# Opamps.net
KiCad netlist of a schematic drawn in Altium Designer
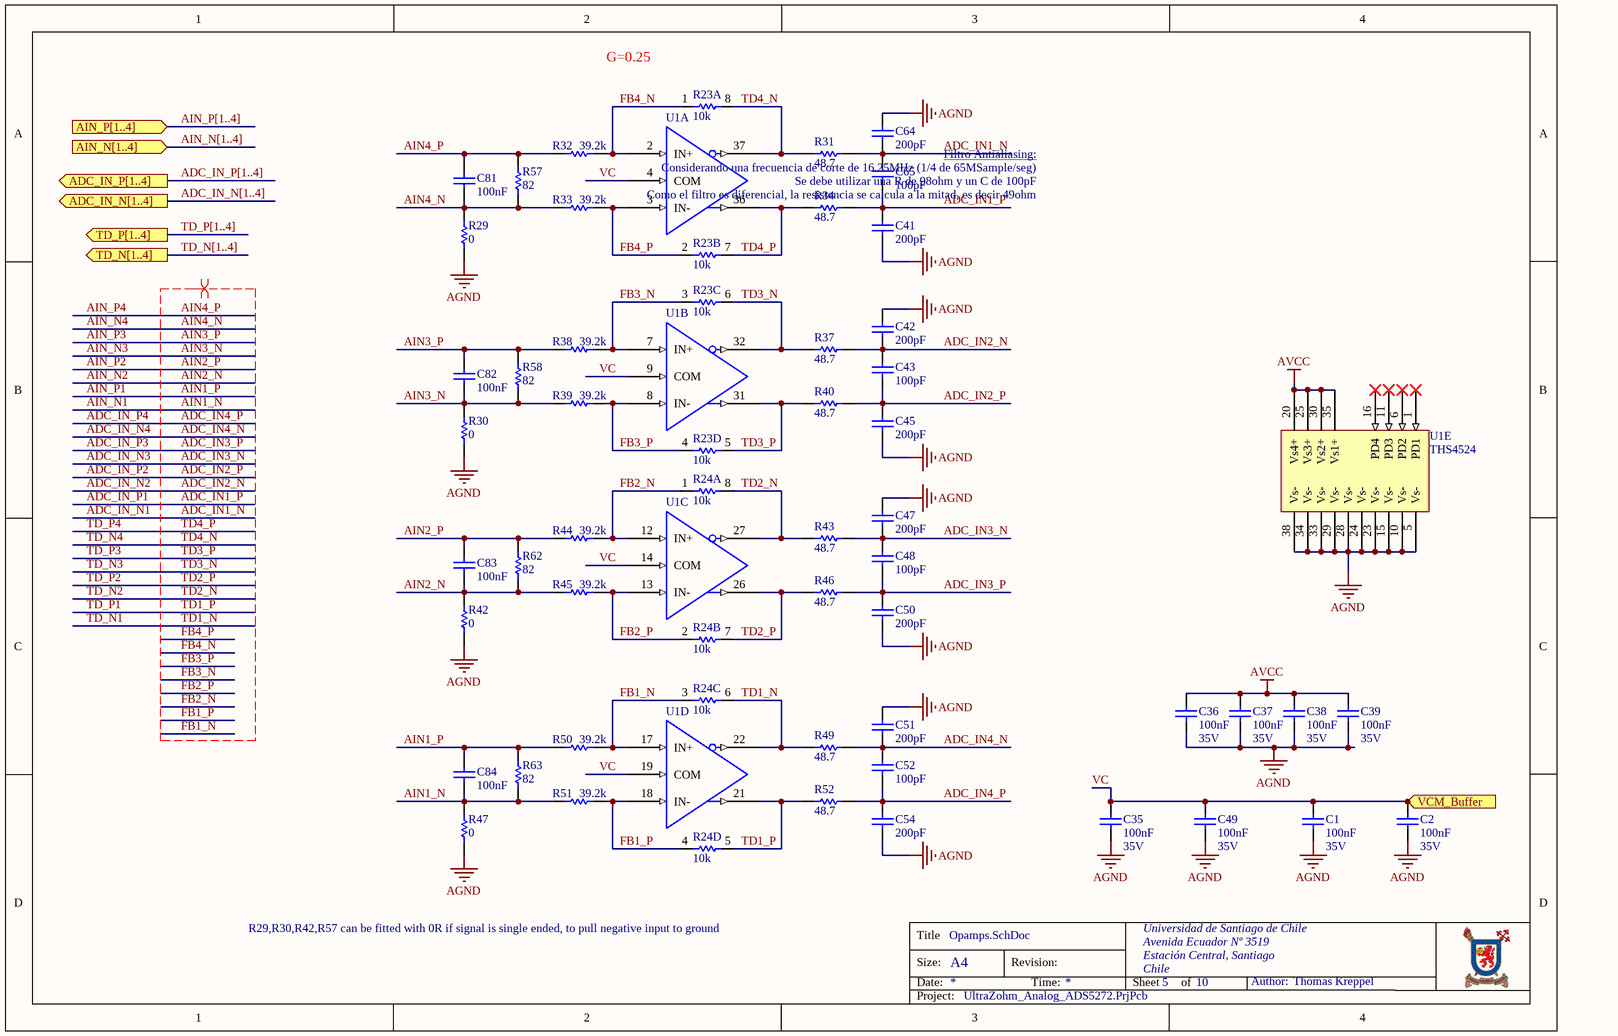
[diagram p0: Opamps.SchDoc]

(export (version "E")
  (design (tool "Eeschema 10.0.6"))
  (components
    (comp (ref "C1")
      (value "100nF")
      (footprint "CAP_0603")
      (description "Capacitor")
      (fields
        (field (name "MPN") "C0603C104M5RACTU")
        (field (name "MF") "KEMET")
        (field (name "VOLTAGE") "35V")
        (field (name "PUBLISHER") "Altium Limited")
      )
      (libsource (lib "Componentes_SOC") (part "Cap_0603"))
    )
    (comp (ref "C2")
      (value "100nF")
      (footprint "CAP_0603")
      (description "Capacitor")
      (fields
        (field (name "MPN") "C0603C104M5RACTU")
        (field (name "MF") "KEMET")
        (field (name "VOLTAGE") "35V")
        (field (name "PUBLISHER") "Altium Limited")
      )
      (libsource (lib "Componentes_SOC") (part "Cap_0603"))
    )
    (comp (ref "C35")
      (value "100nF")
      (footprint "CAP_0603")
      (description "Capacitor")
      (fields
        (field (name "MPN") "C0603C104M5RACTU")
        (field (name "MF") "KEMET")
        (field (name "VOLTAGE") "35V")
        (field (name "PUBLISHER") "Altium Limited")
      )
      (libsource (lib "Componentes_SOC") (part "Cap_0603"))
    )
    (comp (ref "C36")
      (value "100nF")
      (footprint "CAP_0603")
      (description "Capacitor")
      (fields
        (field (name "MPN") "C0603C104M5RACTU")
        (field (name "MF") "KEMET")
        (field (name "VOLTAGE") "35V")
        (field (name "PUBLISHER") "Altium Limited")
      )
      (libsource (lib "Componentes_SOC") (part "Cap_0603"))
    )
    (comp (ref "C37")
      (value "100nF")
      (footprint "CAP_0603")
      (description "Capacitor")
      (fields
        (field (name "MPN") "C0603C104M5RACTU")
        (field (name "MF") "KEMET")
        (field (name "VOLTAGE") "35V")
        (field (name "PUBLISHER") "Altium Limited")
      )
      (libsource (lib "Componentes_SOC") (part "Cap_0603"))
    )
    (comp (ref "C38")
      (value "100nF")
      (footprint "CAP_0603")
      (description "Capacitor")
      (fields
        (field (name "MPN") "C0603C104M5RACTU")
        (field (name "MF") "KEMET")
        (field (name "VOLTAGE") "35V")
        (field (name "PUBLISHER") "Altium Limited")
      )
      (libsource (lib "Componentes_SOC") (part "Cap_0603"))
    )
    (comp (ref "C39")
      (value "100nF")
      (footprint "CAP_0603")
      (description "Capacitor")
      (fields
        (field (name "MPN") "C0603C104M5RACTU")
        (field (name "MF") "KEMET")
        (field (name "VOLTAGE") "35V")
        (field (name "PUBLISHER") "Altium Limited")
      )
      (libsource (lib "Componentes_SOC") (part "Cap_0603"))
    )
    (comp (ref "C41")
      (value "200pF")
      (footprint "CAP_0603")
      (description "Capacitor")
      (fields
        (field (name "MPN") "0603N201J500CT")
        (field (name "MF") "Walsin")
        (field (name "PUBLISHER") "Altium Limited")
      )
      (libsource (lib "Componentes_SOC") (part "Cap_0603"))
    )
    (comp (ref "C42")
      (value "200pF")
      (footprint "CAP_0603")
      (description "Capacitor")
      (fields
        (field (name "MPN") "0603N201J500CT")
        (field (name "MF") "Walsin")
        (field (name "PUBLISHER") "Altium Limited")
      )
      (libsource (lib "Componentes_SOC") (part "Cap_0603"))
    )
    (comp (ref "C43")
      (value "100pF")
      (footprint "CAP_0603")
      (description "Capacitor")
      (fields
        (field (name "MPN") "885012006023")
        (field (name "MF") "Würth Elektronik")
        (field (name "PUBLISHER") "Altium Limited")
      )
      (libsource (lib "Componentes_SOC") (part "Cap_0603"))
    )
    (comp (ref "C45")
      (value "200pF")
      (footprint "CAP_0603")
      (description "Capacitor")
      (fields
        (field (name "MPN") "0603N201J500CT")
        (field (name "MF") "Walsin")
        (field (name "PUBLISHER") "Altium Limited")
      )
      (libsource (lib "Componentes_SOC") (part "Cap_0603"))
    )
    (comp (ref "C47")
      (value "200pF")
      (footprint "CAP_0603")
      (description "Capacitor")
      (fields
        (field (name "MPN") "0603N201J500CT")
        (field (name "MF") "Walsin")
        (field (name "PUBLISHER") "Altium Limited")
      )
      (libsource (lib "Componentes_SOC") (part "Cap_0603"))
    )
    (comp (ref "C48")
      (value "100pF")
      (footprint "CAP_0603")
      (description "Capacitor")
      (fields
        (field (name "MPN") "885012006023")
        (field (name "MF") "Würth Elektronik")
        (field (name "PUBLISHER") "Altium Limited")
      )
      (libsource (lib "Componentes_SOC") (part "Cap_0603"))
    )
    (comp (ref "C49")
      (value "100nF")
      (footprint "CAP_0603")
      (description "Capacitor")
      (fields
        (field (name "MPN") "C0603C104M5RACTU")
        (field (name "MF") "KEMET")
        (field (name "VOLTAGE") "35V")
        (field (name "PUBLISHER") "Altium Limited")
      )
      (libsource (lib "Componentes_SOC") (part "Cap_0603"))
    )
    (comp (ref "C50")
      (value "200pF")
      (footprint "CAP_0603")
      (description "Capacitor")
      (fields
        (field (name "MPN") "0603N201J500CT")
        (field (name "MF") "Walsin")
        (field (name "PUBLISHER") "Altium Limited")
      )
      (libsource (lib "Componentes_SOC") (part "Cap_0603"))
    )
    (comp (ref "C51")
      (value "200pF")
      (footprint "CAP_0603")
      (description "Capacitor")
      (fields
        (field (name "MPN") "0603N201J500CT")
        (field (name "MF") "Walsin")
        (field (name "PUBLISHER") "Altium Limited")
      )
      (libsource (lib "Componentes_SOC") (part "Cap_0603"))
    )
    (comp (ref "C52")
      (value "100pF")
      (footprint "CAP_0603")
      (description "Capacitor")
      (fields
        (field (name "MPN") "885012006023")
        (field (name "MF") "Würth Elektronik")
        (field (name "PUBLISHER") "Altium Limited")
      )
      (libsource (lib "Componentes_SOC") (part "Cap_0603"))
    )
    (comp (ref "C54")
      (value "200pF")
      (footprint "CAP_0603")
      (description "Capacitor")
      (fields
        (field (name "MPN") "0603N201J500CT")
        (field (name "MF") "Walsin")
        (field (name "PUBLISHER") "Altium Limited")
      )
      (libsource (lib "Componentes_SOC") (part "Cap_0603"))
    )
    (comp (ref "C64")
      (value "200pF")
      (footprint "CAP_0603")
      (description "Capacitor")
      (fields
        (field (name "MPN") "0603N201J500CT")
        (field (name "MF") "Walsin")
        (field (name "PUBLISHER") "Altium Limited")
      )
      (libsource (lib "Componentes_SOC") (part "Cap_0603"))
    )
    (comp (ref "C65")
      (value "100pF")
      (footprint "CAP_0603")
      (description "Capacitor")
      (fields
        (field (name "MPN") "885012006023")
        (field (name "MF") "Würth Elektronik")
        (field (name "PUBLISHER") "Altium Limited")
      )
      (libsource (lib "Componentes_SOC") (part "Cap_0603"))
    )
    (comp (ref "C81")
      (value "100nF")
      (footprint "RES_1206")
      (description "Capacitor")
      (fields (field (name "VOLTAGE") "25V") (field (name "MF") "KEMET"))
      (libsource (lib "Componentes_SOC") (part "Cap_1206"))
    )
    (comp (ref "C82")
      (value "100nF")
      (footprint "RES_1206")
      (description "Capacitor")
      (fields (field (name "VOLTAGE") "25V") (field (name "MF") "KEMET"))
      (libsource (lib "Componentes_SOC") (part "Cap_1206"))
    )
    (comp (ref "C83")
      (value "100nF")
      (footprint "RES_1206")
      (description "Capacitor")
      (fields (field (name "VOLTAGE") "25V") (field (name "MF") "KEMET"))
      (libsource (lib "Componentes_SOC") (part "Cap_1206"))
    )
    (comp (ref "C84")
      (value "100nF")
      (footprint "RES_1206")
      (description "Capacitor")
      (fields (field (name "VOLTAGE") "25V") (field (name "MF") "KEMET"))
      (libsource (lib "Componentes_SOC") (part "Cap_1206"))
    )
    (comp (ref "R23")
      (value "10k")
      (footprint "CAC-80P320X160-8N")
      (description "Chip Resistor Array 0606, 4xR")
      (fields (field (name "MANUFACTURER") "Vishay") (field (name "CREATED") "Kreppel_0420"))
      (libsource (lib "Componentes_SOC") (part "ResArray 1206"))
    )
    (comp (ref "R24")
      (value "10k")
      (footprint "CAC-80P320X160-8N")
      (description "Chip Resistor Array 0606, 4xR")
      (fields (field (name "MANUFACTURER") "Vishay") (field (name "CREATED") "Kreppel_0420"))
      (libsource (lib "Componentes_SOC") (part "ResArray 1206"))
    )
    (comp (ref "R29")
      (value "0")
      (footprint "RES_0603")
      (fields (field (name "TOLERANCE") "1%") (field (name "PUBLISHER") "Altium Limited"))
      (libsource (lib "Componentes_SOC") (part "Res0603"))
    )
    (comp (ref "R30")
      (value "0")
      (footprint "RES_0603")
      (fields (field (name "TOLERANCE") "1%") (field (name "PUBLISHER") "Altium Limited"))
      (libsource (lib "Componentes_SOC") (part "Res0603"))
    )
    (comp (ref "R31")
      (value "48.7")
      (footprint "RES_0603")
      (fields (field (name "TOLERANCE") "0.1%") (field (name "PUBLISHER") "Altium Limited"))
      (libsource (lib "Componentes_SOC") (part "Res0603"))
    )
    (comp (ref "R32")
      (value "39.2k")
      (footprint "RES_0603")
      (fields (field (name "TOLERANCE") "0.1%") (field (name "PUBLISHER") "Altium Limited"))
      (libsource (lib "Componentes_SOC") (part "Res0603"))
    )
    (comp (ref "R33")
      (value "39.2k")
      (footprint "RES_0603")
      (fields (field (name "TOLERANCE") "0.1%") (field (name "PUBLISHER") "Altium Limited"))
      (libsource (lib "Componentes_SOC") (part "Res0603"))
    )
    (comp (ref "R34")
      (value "48.7")
      (footprint "RES_0603")
      (fields (field (name "TOLERANCE") "0.1%") (field (name "PUBLISHER") "Altium Limited"))
      (libsource (lib "Componentes_SOC") (part "Res0603"))
    )
    (comp (ref "R37")
      (value "48.7")
      (footprint "RES_0603")
      (fields (field (name "TOLERANCE") "0.1%") (field (name "PUBLISHER") "Altium Limited"))
      (libsource (lib "Componentes_SOC") (part "Res0603"))
    )
    (comp (ref "R38")
      (value "39.2k")
      (footprint "RES_0603")
      (fields (field (name "TOLERANCE") "0.1%") (field (name "PUBLISHER") "Altium Limited"))
      (libsource (lib "Componentes_SOC") (part "Res0603"))
    )
    (comp (ref "R39")
      (value "39.2k")
      (footprint "RES_0603")
      (fields (field (name "TOLERANCE") "0.1%") (field (name "PUBLISHER") "Altium Limited"))
      (libsource (lib "Componentes_SOC") (part "Res0603"))
    )
    (comp (ref "R40")
      (value "48.7")
      (footprint "RES_0603")
      (fields (field (name "TOLERANCE") "0.1%") (field (name "PUBLISHER") "Altium Limited"))
      (libsource (lib "Componentes_SOC") (part "Res0603"))
    )
    (comp (ref "R42")
      (value "0")
      (footprint "RES_0603")
      (fields (field (name "TOLERANCE") "1%") (field (name "PUBLISHER") "Altium Limited"))
      (libsource (lib "Componentes_SOC") (part "Res0603"))
    )
    (comp (ref "R43")
      (value "48.7")
      (footprint "RES_0603")
      (fields (field (name "TOLERANCE") "0.1%") (field (name "PUBLISHER") "Altium Limited"))
      (libsource (lib "Componentes_SOC") (part "Res0603"))
    )
    (comp (ref "R44")
      (value "39.2k")
      (footprint "RES_0603")
      (fields (field (name "TOLERANCE") "0.1%") (field (name "PUBLISHER") "Altium Limited"))
      (libsource (lib "Componentes_SOC") (part "Res0603"))
    )
    (comp (ref "R45")
      (value "39.2k")
      (footprint "RES_0603")
      (fields (field (name "TOLERANCE") "0.1%") (field (name "PUBLISHER") "Altium Limited"))
      (libsource (lib "Componentes_SOC") (part "Res0603"))
    )
    (comp (ref "R46")
      (value "48.7")
      (footprint "RES_0603")
      (fields (field (name "TOLERANCE") "0.1%") (field (name "PUBLISHER") "Altium Limited"))
      (libsource (lib "Componentes_SOC") (part "Res0603"))
    )
    (comp (ref "R47")
      (value "0")
      (footprint "RES_0603")
      (fields (field (name "TOLERANCE") "1%") (field (name "PUBLISHER") "Altium Limited"))
      (libsource (lib "Componentes_SOC") (part "Res0603"))
    )
    (comp (ref "R49")
      (value "48.7")
      (footprint "RES_0603")
      (fields (field (name "TOLERANCE") "0.1%") (field (name "PUBLISHER") "Altium Limited"))
      (libsource (lib "Componentes_SOC") (part "Res0603"))
    )
    (comp (ref "R50")
      (value "39.2k")
      (footprint "RES_0603")
      (fields (field (name "TOLERANCE") "0.1%") (field (name "PUBLISHER") "Altium Limited"))
      (libsource (lib "Componentes_SOC") (part "Res0603"))
    )
    (comp (ref "R51")
      (value "39.2k")
      (footprint "RES_0603")
      (fields (field (name "TOLERANCE") "0.1%") (field (name "PUBLISHER") "Altium Limited"))
      (libsource (lib "Componentes_SOC") (part "Res0603"))
    )
    (comp (ref "R52")
      (value "48.7")
      (footprint "RES_0603")
      (fields (field (name "TOLERANCE") "0.1%") (field (name "PUBLISHER") "Altium Limited"))
      (libsource (lib "Componentes_SOC") (part "Res0603"))
    )
    (comp (ref "R57")
      (value "82")
      (footprint "RES_1206")
      (description "Limiter Resistor")
      (fields (field (name "TOLERANCE") "0.1%") (field (name "PUBLISHER") "Altium Limited"))
      (libsource (lib "Miscellaneous Devices") (part "Res Semi"))
    )
    (comp (ref "R58")
      (value "82")
      (footprint "RES_1206")
      (description "Limiter Resistor")
      (fields (field (name "TOLERANCE") "0.1%") (field (name "PUBLISHER") "Altium Limited"))
      (libsource (lib "Miscellaneous Devices") (part "Res Semi"))
    )
    (comp (ref "R62")
      (value "82")
      (footprint "RES_1206")
      (description "Limiter Resistor")
      (fields (field (name "TOLERANCE") "0.1%") (field (name "PUBLISHER") "Altium Limited"))
      (libsource (lib "Miscellaneous Devices") (part "Res Semi"))
    )
    (comp (ref "R63")
      (value "82")
      (footprint "RES_1206")
      (description "Limiter Resistor")
      (fields (field (name "TOLERANCE") "0.1%") (field (name "PUBLISHER") "Altium Limited"))
      (libsource (lib "Miscellaneous Devices") (part "Res Semi"))
    )
    (comp (ref "U1")
      (value "THS4524")
      (footprint "THS4524 Footprint")
      (description "Quad Channel fully differential Amplilfier")
      (fields (field (name "MANUFACTURER") "Texas Instruments") (field (name "CREATED") "20190720_Kreppel"))
      (libsource (lib "") (part "THS4524_1_1"))
    )
  )
  (nets
    (net (code "1") (name "/ADC_IN_N1") (class "Default")
      (node (ref "C64") (pin "2") (pinfunction "2_2") (pintype "passive"))
      (node (ref "C65") (pin "1") (pinfunction "1_1") (pintype "passive"))
      (node (ref "R31") (pin "1") (pinfunction "1_1") (pintype "passive"))
    )
    (net (code "2") (name "/ADC_IN_N2") (class "Default")
      (node (ref "C42") (pin "2") (pinfunction "2_2") (pintype "passive"))
      (node (ref "C43") (pin "1") (pinfunction "1_1") (pintype "passive"))
      (node (ref "R37") (pin "1") (pinfunction "1_1") (pintype "passive"))
    )
    (net (code "3") (name "/ADC_IN_N3") (class "Default")
      (node (ref "C47") (pin "2") (pinfunction "2_2") (pintype "passive"))
      (node (ref "C48") (pin "1") (pinfunction "1_1") (pintype "passive"))
      (node (ref "R43") (pin "1") (pinfunction "1_1") (pintype "passive"))
    )
    (net (code "4") (name "/ADC_IN_N4") (class "Default")
      (node (ref "C51") (pin "2") (pinfunction "2_2") (pintype "passive"))
      (node (ref "C52") (pin "1") (pinfunction "1_1") (pintype "passive"))
      (node (ref "R49") (pin "1") (pinfunction "1_1") (pintype "passive"))
    )
    (net (code "6") (name "/ADC_IN_P1") (class "Default")
      (node (ref "C41") (pin "1") (pinfunction "1_1") (pintype "passive"))
      (node (ref "C65") (pin "2") (pinfunction "2_2") (pintype "passive"))
      (node (ref "R34") (pin "1") (pinfunction "1_1") (pintype "passive"))
    )
    (net (code "7") (name "/ADC_IN_P2") (class "Default")
      (node (ref "C43") (pin "2") (pinfunction "2_2") (pintype "passive"))
      (node (ref "C45") (pin "1") (pinfunction "1_1") (pintype "passive"))
      (node (ref "R40") (pin "1") (pinfunction "1_1") (pintype "passive"))
    )
    (net (code "8") (name "/ADC_IN_P3") (class "Default")
      (node (ref "C48") (pin "2") (pinfunction "2_2") (pintype "passive"))
      (node (ref "C50") (pin "1") (pinfunction "1_1") (pintype "passive"))
      (node (ref "R46") (pin "1") (pinfunction "1_1") (pintype "passive"))
    )
    (net (code "9") (name "/ADC_IN_P4") (class "Default")
      (node (ref "C52") (pin "2") (pinfunction "2_2") (pintype "passive"))
      (node (ref "C54") (pin "1") (pinfunction "1_1") (pintype "passive"))
      (node (ref "R52") (pin "1") (pinfunction "1_1") (pintype "passive"))
    )
    (net (code "11") (name "/AIN_N1") (class "Default")
      (node (ref "C84") (pin "2") (pinfunction "2_2") (pintype "passive"))
      (node (ref "R47") (pin "1") (pinfunction "1_1") (pintype "passive"))
      (node (ref "R51") (pin "2") (pinfunction "2_2") (pintype "passive"))
      (node (ref "R63") (pin "2") (pinfunction "2_2") (pintype "passive"))
    )
    (net (code "12") (name "/AIN_N2") (class "Default")
      (node (ref "C83") (pin "2") (pinfunction "2_2") (pintype "passive"))
      (node (ref "R42") (pin "1") (pinfunction "1_1") (pintype "passive"))
      (node (ref "R45") (pin "2") (pinfunction "2_2") (pintype "passive"))
      (node (ref "R62") (pin "2") (pinfunction "2_2") (pintype "passive"))
    )
    (net (code "13") (name "/AIN_N3") (class "Default")
      (node (ref "C82") (pin "2") (pinfunction "2_2") (pintype "passive"))
      (node (ref "R30") (pin "1") (pinfunction "1_1") (pintype "passive"))
      (node (ref "R39") (pin "2") (pinfunction "2_2") (pintype "passive"))
      (node (ref "R58") (pin "2") (pinfunction "2_2") (pintype "passive"))
    )
    (net (code "14") (name "/AIN_N4") (class "Default")
      (node (ref "C81") (pin "2") (pinfunction "2_2") (pintype "passive"))
      (node (ref "R29") (pin "1") (pinfunction "1_1") (pintype "passive"))
      (node (ref "R33") (pin "2") (pinfunction "2_2") (pintype "passive"))
      (node (ref "R57") (pin "2") (pinfunction "2_2") (pintype "passive"))
    )
    (net (code "16") (name "/AIN_P1") (class "Default")
      (node (ref "C84") (pin "1") (pinfunction "1_1") (pintype "passive"))
      (node (ref "R50") (pin "2") (pinfunction "2_2") (pintype "passive"))
      (node (ref "R63") (pin "1") (pinfunction "1_1") (pintype "passive"))
    )
    (net (code "17") (name "/AIN_P2") (class "Default")
      (node (ref "C83") (pin "1") (pinfunction "1_1") (pintype "passive"))
      (node (ref "R44") (pin "2") (pinfunction "2_2") (pintype "passive"))
      (node (ref "R62") (pin "1") (pinfunction "1_1") (pintype "passive"))
    )
    (net (code "18") (name "/AIN_P3") (class "Default")
      (node (ref "C82") (pin "1") (pinfunction "1_1") (pintype "passive"))
      (node (ref "R38") (pin "2") (pinfunction "2_2") (pintype "passive"))
      (node (ref "R58") (pin "1") (pinfunction "1_1") (pintype "passive"))
    )
    (net (code "19") (name "/AIN_P4") (class "Default")
      (node (ref "C81") (pin "1") (pinfunction "1_1") (pintype "passive"))
      (node (ref "R32") (pin "2") (pinfunction "2_2") (pintype "passive"))
      (node (ref "R57") (pin "1") (pinfunction "1_1") (pintype "passive"))
    )
    (net (code "21") (name "/FB1_N") (class "Default")
      (node (ref "R24") (pin "3") (pinfunction "1_3") (pintype "passive"))
      (node (ref "R50") (pin "1") (pinfunction "1_1") (pintype "passive"))
      (node (ref "U1") (pin "17") (pinfunction "IN+_17") (pintype "input"))
    )
    (net (code "22") (name "/FB1_P") (class "Default")
      (node (ref "R24") (pin "4") (pinfunction "1_4") (pintype "passive"))
      (node (ref "R51") (pin "1") (pinfunction "1_1") (pintype "passive"))
      (node (ref "U1") (pin "18") (pinfunction "IN-_18") (pintype "input"))
    )
    (net (code "23") (name "/FB2_N") (class "Default")
      (node (ref "R24") (pin "1") (pinfunction "1_1") (pintype "passive"))
      (node (ref "R44") (pin "1") (pinfunction "1_1") (pintype "passive"))
      (node (ref "U1") (pin "12") (pinfunction "IN+_12") (pintype "input"))
    )
    (net (code "24") (name "/FB2_P") (class "Default")
      (node (ref "R24") (pin "2") (pinfunction "1_2") (pintype "passive"))
      (node (ref "R45") (pin "1") (pinfunction "1_1") (pintype "passive"))
      (node (ref "U1") (pin "13") (pinfunction "IN-_13") (pintype "input"))
    )
    (net (code "25") (name "/FB3_N") (class "Default")
      (node (ref "R23") (pin "3") (pinfunction "1_3") (pintype "passive"))
      (node (ref "R38") (pin "1") (pinfunction "1_1") (pintype "passive"))
      (node (ref "U1") (pin "7") (pinfunction "IN+_7") (pintype "input"))
    )
    (net (code "26") (name "/FB3_P") (class "Default")
      (node (ref "R23") (pin "4") (pinfunction "1_4") (pintype "passive"))
      (node (ref "R39") (pin "1") (pinfunction "1_1") (pintype "passive"))
      (node (ref "U1") (pin "8") (pinfunction "IN-_8") (pintype "input"))
    )
    (net (code "27") (name "/FB4_N") (class "Default")
      (node (ref "R23") (pin "1") (pinfunction "1_1") (pintype "passive"))
      (node (ref "R32") (pin "1") (pinfunction "1_1") (pintype "passive"))
      (node (ref "U1") (pin "2") (pinfunction "IN+_2") (pintype "input"))
    )
    (net (code "28") (name "/FB4_P") (class "Default")
      (node (ref "R23") (pin "2") (pinfunction "1_2") (pintype "passive"))
      (node (ref "R33") (pin "1") (pinfunction "1_1") (pintype "passive"))
      (node (ref "U1") (pin "3") (pinfunction "IN-_3") (pintype "input"))
    )
    (net (code "29") (name "/TD_N1") (class "Default")
      (node (ref "R24") (pin "6") (pinfunction "2_6") (pintype "passive"))
      (node (ref "R49") (pin "2") (pinfunction "2_2") (pintype "passive"))
      (node (ref "U1") (pin "22") (pinfunction "OUT-_22") (pintype "output"))
    )
    (net (code "30") (name "/TD_N2") (class "Default")
      (node (ref "R24") (pin "8") (pinfunction "2_8") (pintype "passive"))
      (node (ref "R43") (pin "2") (pinfunction "2_2") (pintype "passive"))
      (node (ref "U1") (pin "27") (pinfunction "OUT-_27") (pintype "output"))
    )
    (net (code "31") (name "/TD_N3") (class "Default")
      (node (ref "R23") (pin "6") (pinfunction "2_6") (pintype "passive"))
      (node (ref "R37") (pin "2") (pinfunction "2_2") (pintype "passive"))
      (node (ref "U1") (pin "32") (pinfunction "OUT-_32") (pintype "output"))
    )
    (net (code "32") (name "/TD_N4") (class "Default")
      (node (ref "R23") (pin "8") (pinfunction "2_8") (pintype "passive"))
      (node (ref "R31") (pin "2") (pinfunction "2_2") (pintype "passive"))
      (node (ref "U1") (pin "37") (pinfunction "OUT-_37") (pintype "output"))
    )
    (net (code "34") (name "/TD_P1") (class "Default")
      (node (ref "R24") (pin "5") (pinfunction "2_5") (pintype "passive"))
      (node (ref "R52") (pin "2") (pinfunction "2_2") (pintype "passive"))
      (node (ref "U1") (pin "21") (pinfunction "OUT+_21") (pintype "output"))
    )
    (net (code "35") (name "/TD_P2") (class "Default")
      (node (ref "R24") (pin "7") (pinfunction "2_7") (pintype "passive"))
      (node (ref "R46") (pin "2") (pinfunction "2_2") (pintype "passive"))
      (node (ref "U1") (pin "26") (pinfunction "OUT+_26") (pintype "output"))
    )
    (net (code "36") (name "/TD_P3") (class "Default")
      (node (ref "R23") (pin "5") (pinfunction "2_5") (pintype "passive"))
      (node (ref "R40") (pin "2") (pinfunction "2_2") (pintype "passive"))
      (node (ref "U1") (pin "31") (pinfunction "OUT+_31") (pintype "output"))
    )
    (net (code "37") (name "/TD_P4") (class "Default")
      (node (ref "R23") (pin "7") (pinfunction "2_7") (pintype "passive"))
      (node (ref "R34") (pin "2") (pinfunction "2_2") (pintype "passive"))
      (node (ref "U1") (pin "36") (pinfunction "OUT+_36") (pintype "output"))
    )
    (net (code "39") (name "/VC") (class "Default")
      (node (ref "C1") (pin "2") (pinfunction "2_2") (pintype "passive"))
      (node (ref "C2") (pin "2") (pinfunction "2_2") (pintype "passive"))
      (node (ref "C35") (pin "2") (pinfunction "2_2") (pintype "passive"))
      (node (ref "C49") (pin "2") (pinfunction "2_2") (pintype "passive"))
      (node (ref "U1") (pin "14") (pinfunction "COM_14") (pintype "input"))
      (node (ref "U1") (pin "19") (pinfunction "COM_19") (pintype "input"))
      (node (ref "U1") (pin "4") (pinfunction "COM_4") (pintype "input"))
      (node (ref "U1") (pin "9") (pinfunction "COM_9") (pintype "input"))
    )
    (net (code "40") (name "AGND") (class "Default")
      (node (ref "C1") (pin "1") (pinfunction "1_1") (pintype "passive"))
      (node (ref "C2") (pin "1") (pinfunction "1_1") (pintype "passive"))
      (node (ref "C35") (pin "1") (pinfunction "1_1") (pintype "passive"))
      (node (ref "C36") (pin "2") (pinfunction "2_2") (pintype "passive"))
      (node (ref "C37") (pin "2") (pinfunction "2_2") (pintype "passive"))
      (node (ref "C38") (pin "2") (pinfunction "2_2") (pintype "passive"))
      (node (ref "C39") (pin "2") (pinfunction "2_2") (pintype "passive"))
      (node (ref "C41") (pin "2") (pinfunction "2_2") (pintype "passive"))
      (node (ref "C42") (pin "1") (pinfunction "1_1") (pintype "passive"))
      (node (ref "C45") (pin "2") (pinfunction "2_2") (pintype "passive"))
      (node (ref "C47") (pin "1") (pinfunction "1_1") (pintype "passive"))
      (node (ref "C49") (pin "1") (pinfunction "1_1") (pintype "passive"))
      (node (ref "C50") (pin "2") (pinfunction "2_2") (pintype "passive"))
      (node (ref "C51") (pin "1") (pinfunction "1_1") (pintype "passive"))
      (node (ref "C54") (pin "2") (pinfunction "2_2") (pintype "passive"))
      (node (ref "C64") (pin "1") (pinfunction "1_1") (pintype "passive"))
      (node (ref "R29") (pin "2") (pinfunction "2_2") (pintype "passive"))
      (node (ref "R30") (pin "2") (pinfunction "2_2") (pintype "passive"))
      (node (ref "R42") (pin "2") (pinfunction "2_2") (pintype "passive"))
      (node (ref "R47") (pin "2") (pinfunction "2_2") (pintype "passive"))
      (node (ref "U1") (pin "10") (pinfunction "Vs-_10") (pintype "power_in"))
      (node (ref "U1") (pin "15") (pinfunction "Vs-_15") (pintype "passive"))
      (node (ref "U1") (pin "23") (pinfunction "Vs-_23") (pintype "power_in"))
      (node (ref "U1") (pin "24") (pinfunction "Vs-_24") (pintype "power_in"))
      (node (ref "U1") (pin "28") (pinfunction "Vs-_28") (pintype "power_in"))
      (node (ref "U1") (pin "29") (pinfunction "Vs-_29") (pintype "power_in"))
      (node (ref "U1") (pin "33") (pinfunction "Vs-_33") (pintype "power_in"))
      (node (ref "U1") (pin "34") (pinfunction "Vs-_34") (pintype "power_in"))
      (node (ref "U1") (pin "38") (pinfunction "Vs-_38") (pintype "power_in"))
      (node (ref "U1") (pin "5") (pinfunction "Vs-_5") (pintype "power_in"))
    )
    (net (code "41") (name "AVCC") (class "Default")
      (node (ref "C36") (pin "1") (pinfunction "1_1") (pintype "passive"))
      (node (ref "C37") (pin "1") (pinfunction "1_1") (pintype "passive"))
      (node (ref "C38") (pin "1") (pinfunction "1_1") (pintype "passive"))
      (node (ref "C39") (pin "1") (pinfunction "1_1") (pintype "passive"))
      (node (ref "U1") (pin "20") (pinfunction "Vs4+_20") (pintype "power_in"))
      (node (ref "U1") (pin "25") (pinfunction "Vs3+_25") (pintype "power_in"))
      (node (ref "U1") (pin "30") (pinfunction "Vs2+_30") (pintype "power_in"))
      (node (ref "U1") (pin "35") (pinfunction "Vs1+_35") (pintype "power_in"))
    )
    (net (code "42") (name "unconnected-(U1E-PD1-Pad1)") (class "Default")
      (node (ref "U1") (pin "1") (pinfunction "PD1_1") (pintype "input+no_connect"))
    )
    (net (code "43") (name "unconnected-(U1E-PD2-Pad6)") (class "Default")
      (node (ref "U1") (pin "6") (pinfunction "PD2_6") (pintype "input+no_connect"))
    )
    (net (code "44") (name "unconnected-(U1E-PD3-Pad11)") (class "Default")
      (node (ref "U1") (pin "11") (pinfunction "PD3_11") (pintype "input+no_connect"))
    )
    (net (code "45") (name "unconnected-(U1E-PD4-Pad16)") (class "Default")
      (node (ref "U1") (pin "16") (pinfunction "PD4_16") (pintype "input+no_connect"))
    )
  )
)
